# Power.net
KiCad netlist of a schematic drawn in Altium Designer
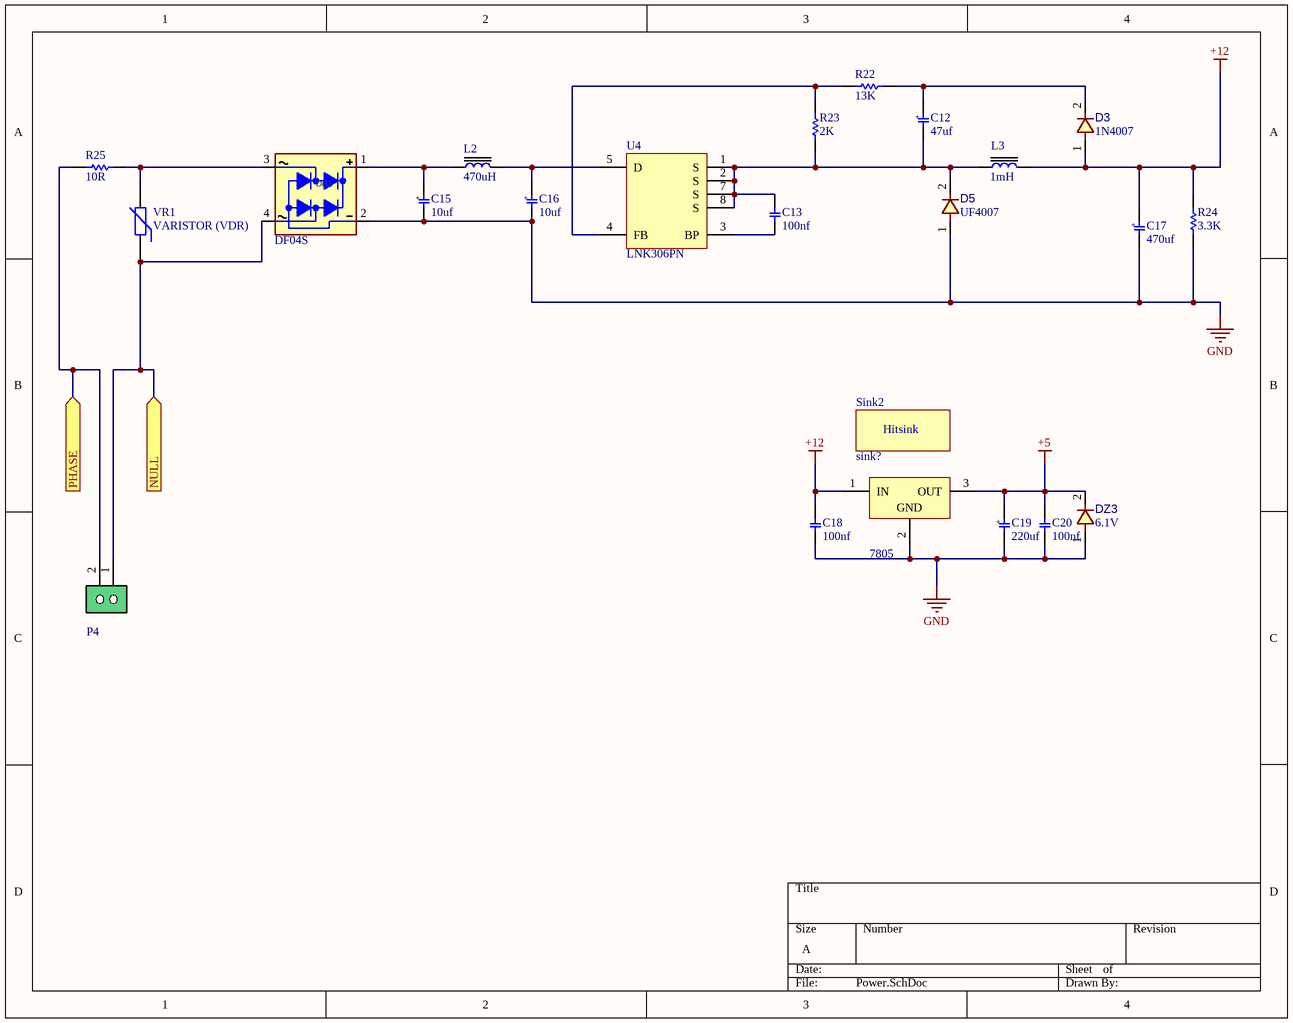
[diagram p0: Power.SchDoc]

(export (version "E")
  (design (tool "Eeschema 10.0.6"))
  (components
    (comp (ref "7805")
      (value "7805CV")
      (footprint "TO220")
      (description "7805")
      (libsource (lib "Regulator") (part "7805"))
    )
    (comp (ref "C12")
      (value "47uf")
      (footprint "C_EL_6X11")
      (description "Capacitor Electrical THD")
      (libsource (lib "Capacitor") (part "Capacitor Electrical THD"))
    )
    (comp (ref "C13")
      (value "100nf")
      (footprint "C1206")
      (description "Capacitor C SMD 1206")
      (libsource (lib "Capacitor") (part "Capacitor C SMD 1206"))
    )
    (comp (ref "C15")
      (value "10uf")
      (footprint "C_EL_10X20")
      (description "Capacitor Electrical THD")
      (libsource (lib "Capacitor") (part "Capacitor Electrical THD"))
    )
    (comp (ref "C16")
      (value "10uf")
      (footprint "C_EL_10X20")
      (description "Capacitor Electrical THD")
      (libsource (lib "Capacitor") (part "Capacitor Electrical THD"))
    )
    (comp (ref "C17")
      (value "470uf")
      (footprint "C_EL_10X20")
      (description "Capacitor Electrical THD")
      (libsource (lib "Capacitor") (part "Capacitor Electrical THD"))
    )
    (comp (ref "C18")
      (value "100nf")
      (footprint "C1206")
      (description "Capacitor C SMD 1206")
      (libsource (lib "Capacitor") (part "Capacitor C SMD 1206"))
    )
    (comp (ref "C19")
      (value "220uf")
      (footprint "C_EL_5X7")
      (description "Capacitor Electrical THD")
      (libsource (lib "Capacitor") (part "Capacitor Electrical THD"))
    )
    (comp (ref "C20")
      (value "100nf")
      (footprint "C1206")
      (description "Capacitor C SMD 1206")
      (libsource (lib "Capacitor") (part "Capacitor C SMD 1206"))
    )
    (comp (ref "D3")
      (value "1N4007")
      (footprint "D_SMA")
      (description "DIODE, GENERAL PURPOSE, 1000V/1A")
      (fields (field (name "Comment") "1N4007 SMD M7"))
      (libsource (lib "Diode") (part "1N4007 SMD M7"))
    )
    (comp (ref "D5")
      (value "UF4007")
      (footprint "D_SMA")
      (description "DIODE, GENERAL PURPOSE, 1000V/1A")
      (fields (field (name "Comment") "1N4007 SMD M7"))
      (libsource (lib "Diode") (part "1N4007 SMD M7"))
    )
    (comp (ref "DB1")
      (value "DF04S")
      (footprint "DBRG_DIPSMD")
      (description "DIODE, BRIDGE,")
      (fields (field (name "Comment") "Diode Bridge SMD"))
      (libsource (lib "Diode") (part "Diode Bridge SMD"))
    )
    (comp (ref "DZ3")
      (value "6.1V")
      (footprint "D_SOD80")
      (description "DIODE, FAST SWTICHING, 0.3A, 0.5W")
      (fields (field (name "Comment") "1N4148 SMD"))
      (libsource (lib "Diode") (part "1N4148 SMD"))
    )
    (comp (ref "L2")
      (value "470uH")
      (footprint "LT_AX04")
      (description "Inductor THD")
      (libsource (lib "Inductor") (part "Inductor THD"))
    )
    (comp (ref "L3")
      (value "1mH")
      (footprint "LT_C10")
      (description "Inductor THD")
      (libsource (lib "Inductor") (part "Inductor THD"))
    )
    (comp (ref "P4")
      (value "Phoenix 2")
      (footprint "PRKR2A")
      (libsource (lib "Connector") (part "Phoenix 2"))
    )
    (comp (ref "R22")
      (value "13K")
      (footprint "Res-(1/4)")
      (description "Resistor THD")
      (libsource (lib "Resistor") (part "Resistor THD"))
    )
    (comp (ref "R23")
      (value "2K")
      (footprint "Res-(1/4)")
      (description "Resistor THD")
      (libsource (lib "Resistor") (part "Resistor THD"))
    )
    (comp (ref "R24")
      (value "3.3K")
      (footprint "SMD-1206-RES")
      (description "Resistor SMD 1206")
      (libsource (lib "Resistor") (part "Resistor SMD 1206"))
    )
    (comp (ref "R25")
      (value "10R")
      (footprint "R2W_AX08")
      (description "Resistor THD")
      (libsource (lib "Resistor") (part "Resistor THD"))
    )
    (comp (ref "Sink2")
      (value "sink?")
      (footprint "heatsink (4)")
      (libsource (lib "Heatsink") (part "Hitsink"))
    )
    (comp (ref "U4")
      (value "LNK306PN")
      (footprint "PI-DIP-8B")
      (fields (field (name "MANUFACTURER") "Power Integrations"))
      (libsource (lib "lnk306") (part "CMP-2000-06570-1"))
    )
    (comp (ref "VR1")
      (value "VARISTOR (VDR)")
      (footprint "Varistor Short  Vertical")
      (description "VARISTORS")
      (libsource (lib "Varistor (VDR)") (part "VARISTOR (VDR)"))
    )
  )
  (nets
    (net (code "1") (name "+5") (class "Default")
      (node (ref "7805") (pin "3") (pinfunction "OUT_3") (pintype "power_in"))
      (node (ref "C19") (pin "1") (pinfunction "1_1") (pintype "passive"))
      (node (ref "C20") (pin "2") (pinfunction "2_2") (pintype "passive"))
      (node (ref "DZ3") (pin "2") (pinfunction "2_2") (pintype "passive"))
    )
    (net (code "2") (name "+12") (class "Default")
      (node (ref "7805") (pin "1") (pinfunction "IN_1") (pintype "power_in"))
      (node (ref "C17") (pin "1") (pinfunction "1_1") (pintype "passive"))
      (node (ref "C18") (pin "2") (pinfunction "2_2") (pintype "passive"))
      (node (ref "D3") (pin "1") (pinfunction "1_1") (pintype "passive"))
      (node (ref "L3") (pin "2") (pinfunction "2_2") (pintype "passive"))
      (node (ref "R24") (pin "2") (pinfunction "2_2") (pintype "passive"))
    )
    (net (code "3") (name "/NULL") (class "Default")
      (node (ref "DB1") (pin "4") (pinfunction "ACIN1_4") (pintype "passive"))
      (node (ref "P4") (pin "1") (pinfunction "1_1") (pintype "passive"))
      (node (ref "VR1") (pin "1") (pinfunction "1_1") (pintype "passive"))
    )
    (net (code "4") (name "/PHASE") (class "Default")
      (node (ref "P4") (pin "2") (pinfunction "2_2") (pintype "passive"))
      (node (ref "R25") (pin "1") (pinfunction "1_1") (pintype "passive"))
    )
    (net (code "5") (name "GND") (class "Default")
      (node (ref "7805") (pin "2") (pinfunction "GND_2") (pintype "power_in"))
      (node (ref "C15") (pin "2") (pinfunction "2_2") (pintype "passive"))
      (node (ref "C16") (pin "2") (pinfunction "2_2") (pintype "passive"))
      (node (ref "C17") (pin "2") (pinfunction "2_2") (pintype "passive"))
      (node (ref "C18") (pin "1") (pinfunction "1_1") (pintype "passive"))
      (node (ref "C19") (pin "2") (pinfunction "2_2") (pintype "passive"))
      (node (ref "C20") (pin "1") (pinfunction "1_1") (pintype "passive"))
      (node (ref "D5") (pin "1") (pinfunction "1_1") (pintype "passive"))
      (node (ref "DB1") (pin "2") (pinfunction "DCOUT-_2") (pintype "passive"))
      (node (ref "DZ3") (pin "1") (pinfunction "1_1") (pintype "passive"))
      (node (ref "R24") (pin "1") (pinfunction "1_1") (pintype "passive"))
    )
    (net (code "6") (name "Net-(C12-Pad1)") (class "Default")
      (node (ref "C12") (pin "1") (pinfunction "1_1") (pintype "passive"))
      (node (ref "D3") (pin "2") (pinfunction "2_2") (pintype "passive"))
      (node (ref "R22") (pin "2") (pinfunction "2_2") (pintype "passive"))
    )
    (net (code "7") (name "Net-(C12-Pad2)") (class "Default")
      (node (ref "C12") (pin "2") (pinfunction "2_2") (pintype "passive"))
      (node (ref "C13") (pin "2") (pinfunction "2_2") (pintype "passive"))
      (node (ref "D5") (pin "2") (pinfunction "2_2") (pintype "passive"))
      (node (ref "L3") (pin "1") (pinfunction "1_1") (pintype "passive"))
      (node (ref "R23") (pin "1") (pinfunction "1_1") (pintype "passive"))
      (node (ref "U4") (pin "1") (pinfunction "S_1") (pintype "passive"))
      (node (ref "U4") (pin "2") (pinfunction "S_2") (pintype "passive"))
      (node (ref "U4") (pin "7") (pinfunction "S_7") (pintype "passive"))
      (node (ref "U4") (pin "8") (pinfunction "S_8") (pintype "passive"))
    )
    (net (code "8") (name "Net-(DB1-ACIN2)") (class "Default")
      (node (ref "DB1") (pin "3") (pinfunction "ACIN2_3") (pintype "passive"))
      (node (ref "R25") (pin "2") (pinfunction "2_2") (pintype "passive"))
      (node (ref "VR1") (pin "2") (pinfunction "2_2") (pintype "passive"))
    )
    (net (code "9") (name "Net-(DB1-DCOUT+)") (class "Default")
      (node (ref "C15") (pin "1") (pinfunction "1_1") (pintype "passive"))
      (node (ref "DB1") (pin "1") (pinfunction "DCOUT+_1") (pintype "passive"))
      (node (ref "L2") (pin "1") (pinfunction "1_1") (pintype "passive"))
    )
    (net (code "10") (name "Net-(U4-BP)") (class "Default")
      (node (ref "C13") (pin "1") (pinfunction "1_1") (pintype "passive"))
      (node (ref "U4") (pin "3") (pinfunction "BP_3") (pintype "passive"))
    )
    (net (code "11") (name "Net-(U4-D)") (class "Default")
      (node (ref "C16") (pin "1") (pinfunction "1_1") (pintype "passive"))
      (node (ref "L2") (pin "2") (pinfunction "2_2") (pintype "passive"))
      (node (ref "U4") (pin "5") (pinfunction "D_5") (pintype "passive"))
    )
    (net (code "12") (name "Net-(U4-FB)") (class "Default")
      (node (ref "R22") (pin "1") (pinfunction "1_1") (pintype "passive"))
      (node (ref "R23") (pin "2") (pinfunction "2_2") (pintype "passive"))
      (node (ref "U4") (pin "4") (pinfunction "FB_4") (pintype "passive"))
    )
  )
)
